# SM1.net
KiCad netlist of a schematic drawn in Altium Designer
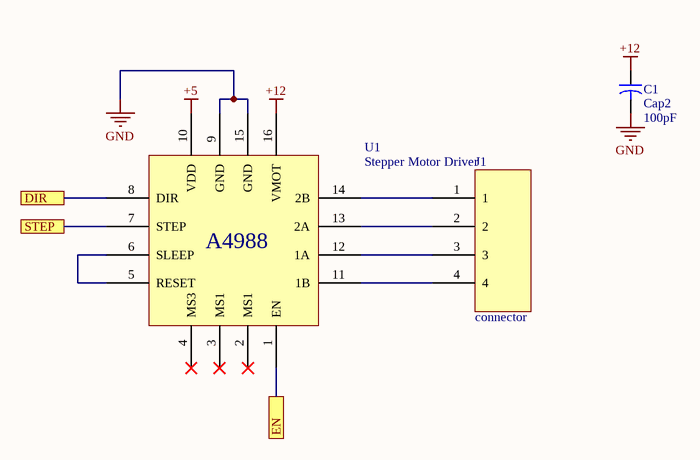
[diagram p0: SM1.SchDoc]

(export (version "E")
  (design (tool "Eeschema 10.0.6"))
  (components
    (comp (ref "C1")
      (value "Cap2")
      (footprint "CAPR5-4X5")
      (description "Capacitor")
      (fields (field (name "ALTIUM_VALUE") "100pF") (field (name "PUBLISHER") "Altium Limited"))
      (libsource (lib "Miscellaneous Devices") (part "Cap2"))
    )
    (comp (ref "J1") (value "connector") (footprint "JST_4P") (libsource (lib "Schlib") (part "JST_4P")))
    (comp (ref "U1")
      (value "Stepper Motor Driver")
      (footprint "A4988")
      (libsource (lib "Schlib") (part "A4988"))
    )
  )
  (nets
    (net (code "1") (name "+5") (class "Default")
      (node (ref "U1") (pin "10") (pinfunction "VDD_10") (pintype "passive"))
    )
    (net (code "2") (name "+12") (class "Default")
      (node (ref "C1") (pin "1") (pinfunction "1_1") (pintype "passive"))
      (node (ref "U1") (pin "16") (pinfunction "VMOT_16") (pintype "passive"))
    )
    (net (code "3") (name "/DIR") (class "Default")
      (node (ref "U1") (pin "8") (pinfunction "DIR_8") (pintype "passive"))
    )
    (net (code "4") (name "/EN") (class "Default")
      (node (ref "U1") (pin "1") (pinfunction "EN_1") (pintype "passive"))
    )
    (net (code "5") (name "/STEP") (class "Default")
      (node (ref "U1") (pin "7") (pinfunction "STEP_7") (pintype "passive"))
    )
    (net (code "6") (name "GND") (class "Default")
      (node (ref "C1") (pin "2") (pinfunction "2_2") (pintype "passive"))
      (node (ref "U1") (pin "15") (pinfunction "GND_15") (pintype "passive"))
      (node (ref "U1") (pin "9") (pinfunction "GND_9") (pintype "passive"))
    )
    (net (code "7") (name "Net-(U1-1A)") (class "Default")
      (node (ref "J1") (pin "3") (pinfunction "3_3") (pintype "passive"))
      (node (ref "U1") (pin "12") (pinfunction "1A_12") (pintype "passive"))
    )
    (net (code "8") (name "Net-(U1-1B)") (class "Default")
      (node (ref "J1") (pin "4") (pinfunction "4_4") (pintype "passive"))
      (node (ref "U1") (pin "11") (pinfunction "1B_11") (pintype "passive"))
    )
    (net (code "9") (name "Net-(U1-2A)") (class "Default")
      (node (ref "J1") (pin "2") (pinfunction "2_2") (pintype "passive"))
      (node (ref "U1") (pin "13") (pinfunction "2A_13") (pintype "passive"))
    )
    (net (code "10") (name "Net-(U1-2B)") (class "Default")
      (node (ref "J1") (pin "1") (pinfunction "1_1") (pintype "passive"))
      (node (ref "U1") (pin "14") (pinfunction "2B_14") (pintype "passive"))
    )
    (net (code "11") (name "Net-(U1-RESET)") (class "Default")
      (node (ref "U1") (pin "5") (pinfunction "RESET_5") (pintype "passive"))
      (node (ref "U1") (pin "6") (pinfunction "SLEEP_6") (pintype "passive"))
    )
    (net (code "12") (name "unconnected-(U1-MS1-Pad2)") (class "Default")
      (node (ref "U1") (pin "2") (pinfunction "MS1_2") (pintype "passive+no_connect"))
    )
    (net (code "13") (name "unconnected-(U1-MS1-Pad3)") (class "Default")
      (node (ref "U1") (pin "3") (pinfunction "MS1_3") (pintype "passive+no_connect"))
    )
    (net (code "14") (name "unconnected-(U1-MS3-Pad4)") (class "Default")
      (node (ref "U1") (pin "4") (pinfunction "MS3_4") (pintype "passive+no_connect"))
    )
  )
)
